# MMA7660-v10.net
KiCad netlist of a schematic drawn in EAGLE
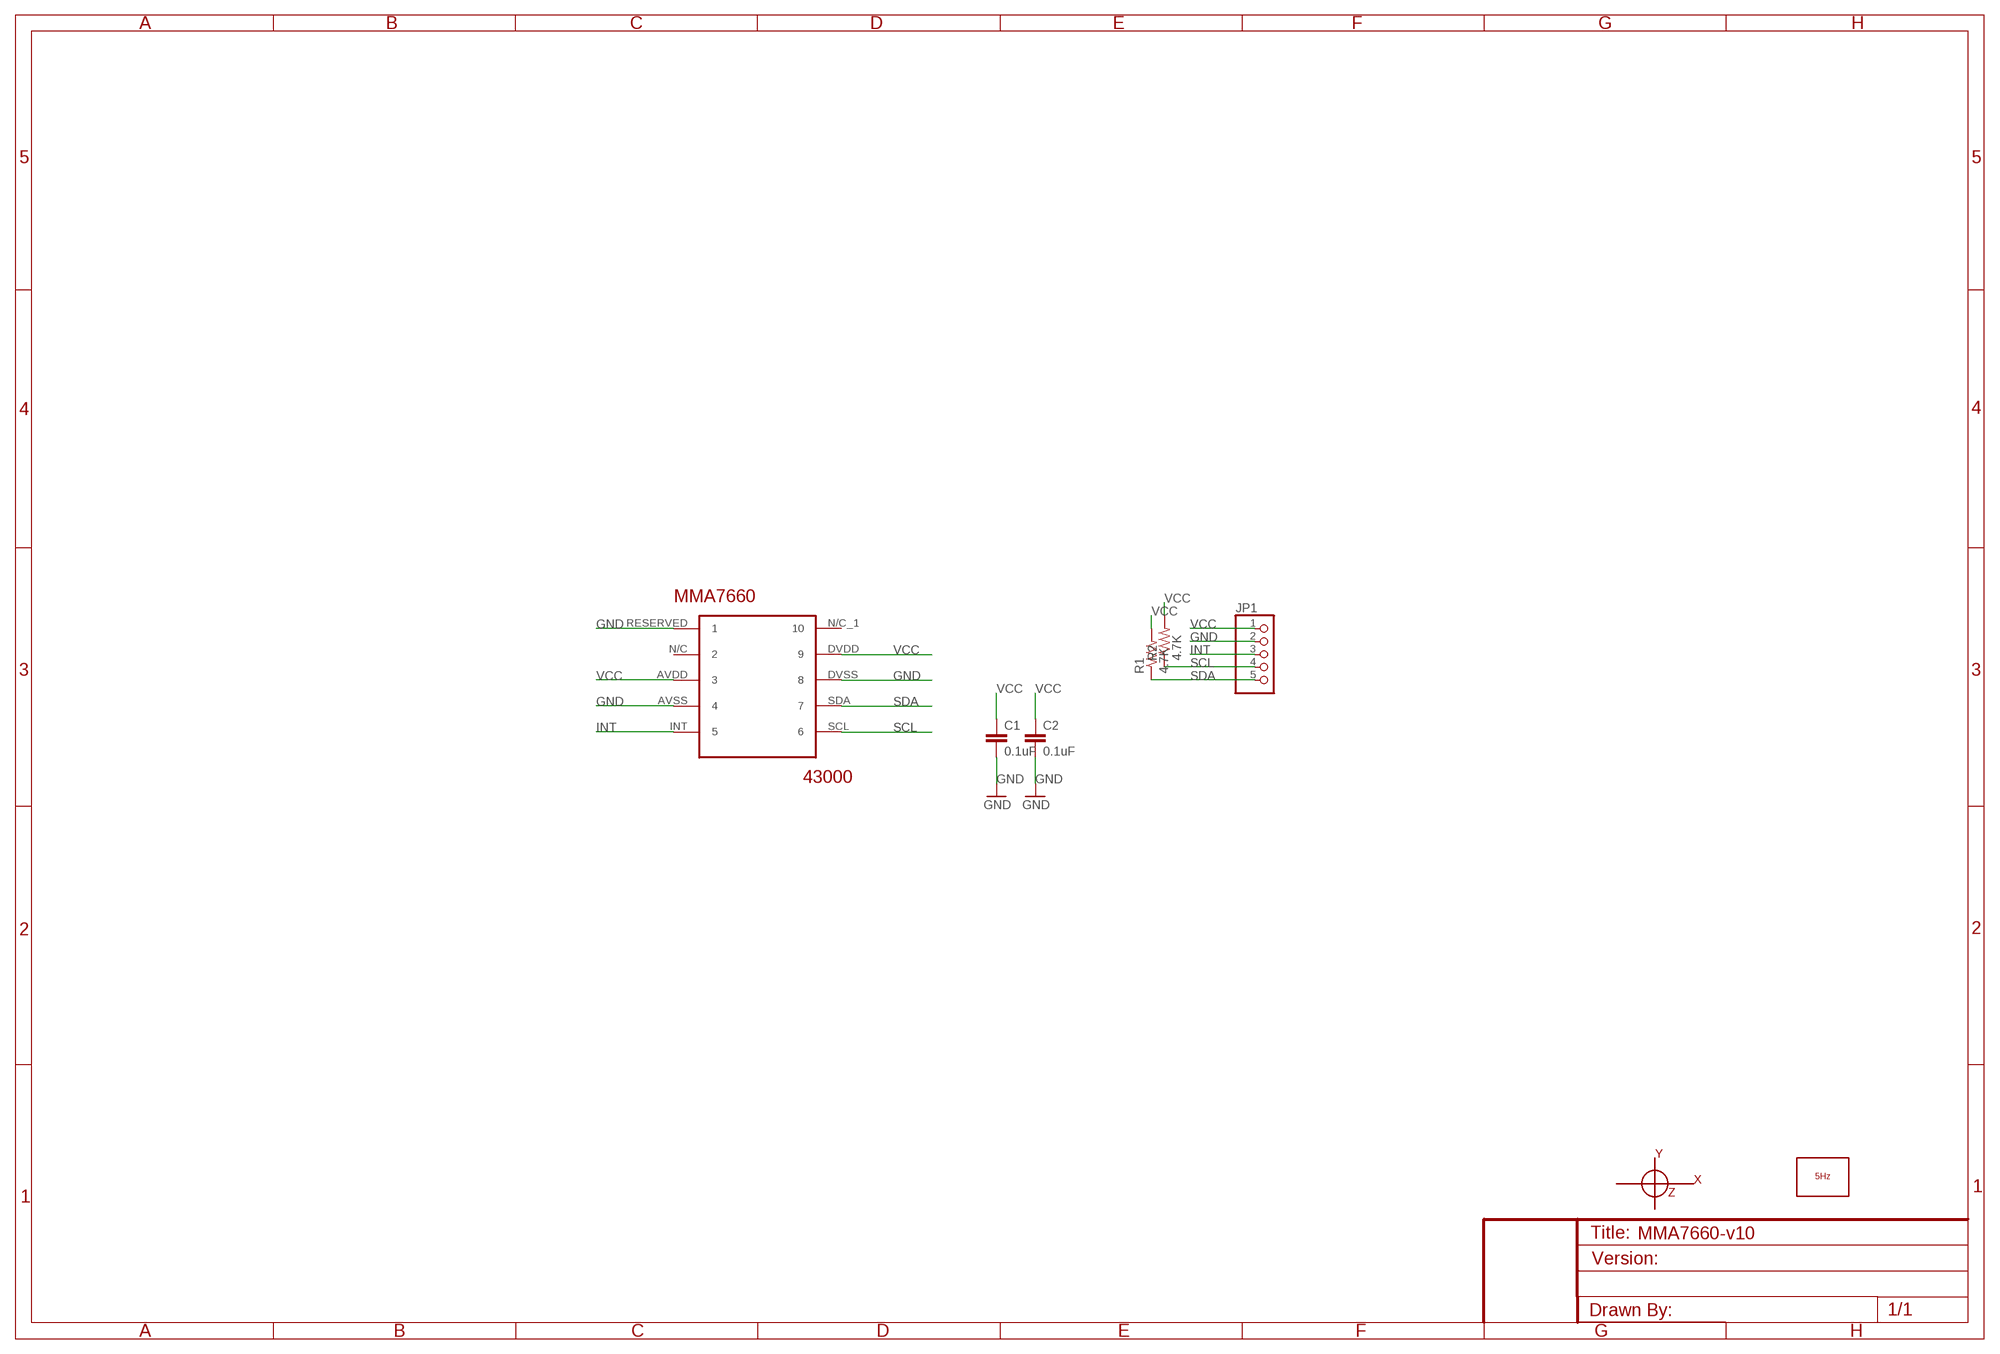
[diagram p0: schematic, sheet 1]

(export (version "E")
  (design (tool "Eeschema 10.0.6"))
  (components
    (comp (ref "C1")
      (value "0.1uF")
      (footprint "eagle-import:0603-CAP")
      (libsource (lib "eagle-import") (part "CAP0603-CAP"))
    )
    (comp (ref "C2")
      (value "0.1uF")
      (footprint "eagle-import:0603-CAP")
      (libsource (lib "eagle-import") (part "CAP0603-CAP"))
    )
    (comp (ref "JP1")
      (value "PINHD-1X5")
      (footprint "eagle-import:1X05")
      (libsource (lib "eagle-import") (part "PINHD-1X5"))
    )
    (comp (ref "LOGO1")
      (value "LOGO_5HZ_H_5MM")
      (footprint "eagle-import:5HZ_LOGO_H_5MM")
      (libsource (lib "eagle-import") (part "LOGO_5HZ_H_5MM"))
    )
    (comp (ref "MMA7660")
      (value "43000")
      (footprint "eagle-import:MMA7660FC")
      (libsource (lib "eagle-import") (part "MMA7660FC"))
    )
    (comp (ref "R1")
      (value "4.7K")
      (footprint "eagle-import:1_6W-RES")
      (libsource (lib "eagle-import") (part "RESISTORPTH-1/6W"))
    )
    (comp (ref "R2")
      (value "4.7K")
      (footprint "eagle-import:1_6W-RES")
      (libsource (lib "eagle-import") (part "RESISTORPTH-1/6W"))
    )
    (comp (ref "U$4")
      (value "EJES_CARTESIANO_5MM")
      (footprint "eagle-import:EJE_CARTESIANO_5MM")
      (libsource (lib "eagle-import") (part "EJES_CARTESIANO_5MM"))
    )
  )
  (nets
    (net (code "1") (name "/INT") (class "Default")
      (node (ref "JP1") (pin "3") (pinfunction "3_3") (pintype "passive"))
      (node (ref "MMA7660") (pin "INT") (pinfunction "5_INT") (pintype "bidirectional"))
    )
    (net (code "2") (name "/SCL") (class "Default")
      (node (ref "JP1") (pin "4") (pinfunction "4_4") (pintype "passive"))
      (node (ref "MMA7660") (pin "SCL") (pinfunction "6_SCL") (pintype "bidirectional"))
      (node (ref "R2") (pin "1") (pinfunction "1_1") (pintype "passive"))
    )
    (net (code "3") (name "/SDA") (class "Default")
      (node (ref "JP1") (pin "5") (pinfunction "5_5") (pintype "passive"))
      (node (ref "MMA7660") (pin "SDA") (pinfunction "7_SDA") (pintype "bidirectional"))
      (node (ref "R1") (pin "1") (pinfunction "1_1") (pintype "passive"))
    )
    (net (code "4") (name "/VCC") (class "Default")
      (node (ref "C1") (pin "1") (pinfunction "1_1") (pintype "passive"))
      (node (ref "C2") (pin "1") (pinfunction "1_1") (pintype "passive"))
      (node (ref "JP1") (pin "1") (pinfunction "1_1") (pintype "passive"))
      (node (ref "MMA7660") (pin "AVDD") (pinfunction "3_AVDD") (pintype "bidirectional"))
      (node (ref "MMA7660") (pin "DVDD") (pinfunction "9_DVDD") (pintype "bidirectional"))
      (node (ref "R1") (pin "2") (pinfunction "2_2") (pintype "passive"))
      (node (ref "R2") (pin "2") (pinfunction "2_2") (pintype "passive"))
    )
    (net (code "5") (name "GND") (class "Default")
      (node (ref "C1") (pin "2") (pinfunction "2_2") (pintype "passive"))
      (node (ref "C2") (pin "2") (pinfunction "2_2") (pintype "passive"))
      (node (ref "JP1") (pin "2") (pinfunction "2_2") (pintype "passive"))
      (node (ref "MMA7660") (pin "AVSS") (pinfunction "4_AVSS") (pintype "bidirectional"))
      (node (ref "MMA7660") (pin "DVSS") (pinfunction "8_DVSS") (pintype "bidirectional"))
      (node (ref "MMA7660") (pin "RESERVED") (pinfunction "1_RESERVED") (pintype "bidirectional"))
    )
    (net (code "6") (name "unconnected-(MMA7660-2-PadN{slash}C)") (class "Default")
      (node (ref "MMA7660") (pin "N/C") (pinfunction "2_N/C") (pintype "bidirectional"))
    )
    (net (code "7") (name "unconnected-(MMA7660-10-PadN{slash}C_1)") (class "Default")
      (node (ref "MMA7660") (pin "N/C_1") (pinfunction "10_N/C_1") (pintype "bidirectional"))
    )
  )
)
